# Input-Comparator.net
KiCad netlist of a schematic drawn in Altium Designer
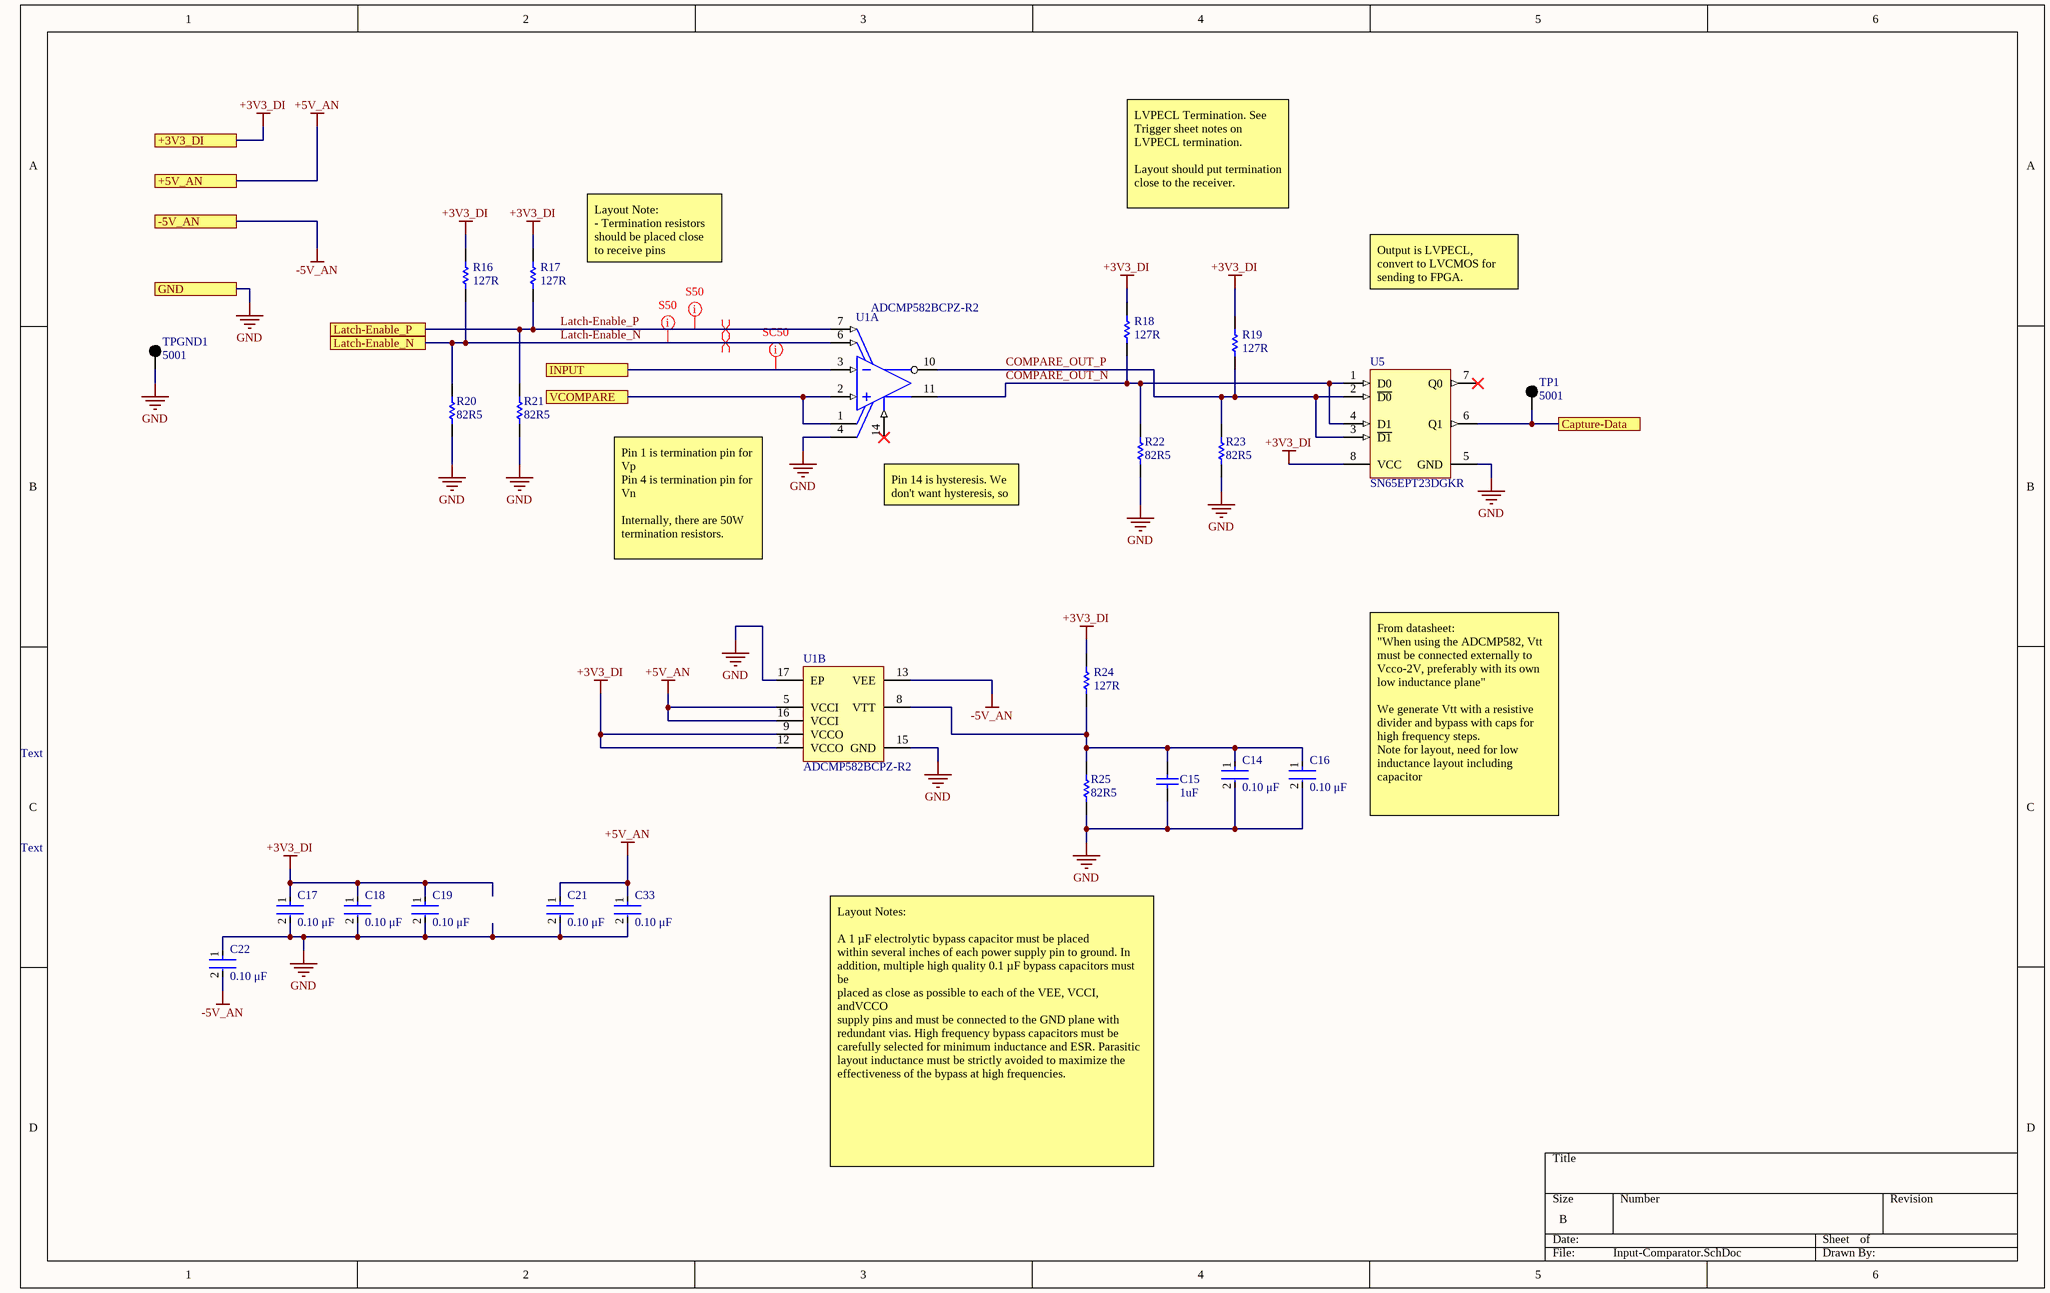
[diagram p0: Input-Comparator.SchDoc]

(export (version "E")
  (design (tool "Eeschema 10.0.6"))
  (components
    (comp (ref "C14")
      (value "C0402C104K8PACTU")
      (footprint "FP-C0402-BB-MFG")
      (description "CAP CER 0.1UF 10V X5R 0402")
      (fields
        (field (name "CAPACITANCE") "0.10 μF")
        (field (name "MANUFACTURER") "Kemet")
        (field (name "TOLERANCE") "0.1")
      )
      (libsource (lib "Altium Content Vault") (part "b4654b650e69147ec39a6b967a45e02"))
    )
    (comp (ref "C15")
      (value "1uF")
      (footprint "CAPC2013X100X50NL20T25")
      (fields (field (name "PART NUMBER") "C0805X105K3RACTU") (field (name "MANUFACTURER") "Kemet"))
      (libsource (lib "Altium Content Vault") (part "CAP"))
    )
    (comp (ref "C16")
      (value "C0402C104K8PACTU")
      (footprint "FP-C0402-BB-MFG")
      (description "CAP CER 0.1UF 10V X5R 0402")
      (fields
        (field (name "CAPACITANCE") "0.10 μF")
        (field (name "MANUFACTURER") "Kemet")
        (field (name "TOLERANCE") "0.1")
      )
      (libsource (lib "Altium Content Vault") (part "b4654b650e69147ec39a6b967a45e02"))
    )
    (comp (ref "C17")
      (value "C0402C104K8PACTU")
      (footprint "FP-C0402-BB-MFG")
      (description "CAP CER 0.1UF 10V X5R 0402")
      (fields
        (field (name "CAPACITANCE") "0.10 μF")
        (field (name "MANUFACTURER") "Kemet")
        (field (name "TOLERANCE") "0.1")
      )
      (libsource (lib "Altium Content Vault") (part "b4654b650e69147ec39a6b967a45e02"))
    )
    (comp (ref "C18")
      (value "C0402C104K8PACTU")
      (footprint "FP-C0402-BB-MFG")
      (description "CAP CER 0.1UF 10V X5R 0402")
      (fields
        (field (name "CAPACITANCE") "0.10 μF")
        (field (name "MANUFACTURER") "Kemet")
        (field (name "TOLERANCE") "0.1")
      )
      (libsource (lib "Altium Content Vault") (part "b4654b650e69147ec39a6b967a45e02"))
    )
    (comp (ref "C19")
      (value "C0402C104K8PACTU")
      (footprint "FP-C0402-BB-MFG")
      (description "CAP CER 0.1UF 10V X5R 0402")
      (fields
        (field (name "CAPACITANCE") "0.10 μF")
        (field (name "MANUFACTURER") "Kemet")
        (field (name "TOLERANCE") "0.1")
      )
      (libsource (lib "Altium Content Vault") (part "b4654b650e69147ec39a6b967a45e02"))
    )
    (comp (ref "C21")
      (value "C0402C104K8PACTU")
      (footprint "FP-C0402-BB-MFG")
      (description "CAP CER 0.1UF 10V X5R 0402")
      (fields
        (field (name "CAPACITANCE") "0.10 μF")
        (field (name "MANUFACTURER") "Kemet")
        (field (name "TOLERANCE") "0.1")
      )
      (libsource (lib "Altium Content Vault") (part "b4654b650e69147ec39a6b967a45e02"))
    )
    (comp (ref "C22")
      (value "C0402C104K8PACTU")
      (footprint "FP-C0402-BB-MFG")
      (description "CAP CER 0.1UF 10V X5R 0402")
      (fields
        (field (name "CAPACITANCE") "0.10 μF")
        (field (name "MANUFACTURER") "Kemet")
        (field (name "TOLERANCE") "0.1")
      )
      (libsource (lib "Altium Content Vault") (part "b4654b650e69147ec39a6b967a45e02"))
    )
    (comp (ref "C33")
      (value "C0402C104K8PACTU")
      (footprint "FP-C0402-BB-MFG")
      (description "CAP CER 0.1UF 10V X5R 0402")
      (fields
        (field (name "CAPACITANCE") "0.10 μF")
        (field (name "MANUFACTURER") "Kemet")
        (field (name "TOLERANCE") "0.1")
      )
      (libsource (lib "Altium Content Vault") (part "b4654b650e69147ec39a6b967a45e02"))
    )
    (comp (ref "R16")
      (value "127R")
      (footprint "RESC1005X40X25LL05T10")
      (fields (field (name "MANUFACTURER") "Yageo / Phycomp") (field (name "PART NUMBER") "RC0402FR-07127RL"))
      (libsource (lib "Altium Content Vault") (part "RES"))
    )
    (comp (ref "R17")
      (value "127R")
      (footprint "RESC1005X40X25LL05T10")
      (fields (field (name "MANUFACTURER") "Yageo / Phycomp") (field (name "PART NUMBER") "RC0402FR-07127RL"))
      (libsource (lib "Altium Content Vault") (part "RES"))
    )
    (comp (ref "R18")
      (value "127R")
      (footprint "RESC1005X40X25LL05T10")
      (fields (field (name "MANUFACTURER") "Yageo / Phycomp") (field (name "PART NUMBER") "RC0402FR-07127RL"))
      (libsource (lib "Altium Content Vault") (part "RES"))
    )
    (comp (ref "R19")
      (value "127R")
      (footprint "RESC1005X40X25LL05T10")
      (fields (field (name "MANUFACTURER") "Yageo / Phycomp") (field (name "PART NUMBER") "RC0402FR-07127RL"))
      (libsource (lib "Altium Content Vault") (part "RES"))
    )
    (comp (ref "R20")
      (value "82R5")
      (footprint "RESC1005X40X25LL05T10")
      (fields (field (name "PART NUMBER") "RC0402FR-0782R5L") (field (name "MANUFACTURER") "Yageo / Phycomp"))
      (libsource (lib "Altium Content Vault") (part "RES"))
    )
    (comp (ref "R21")
      (value "82R5")
      (footprint "RESC1005X40X25LL05T10")
      (fields (field (name "PART NUMBER") "RC0402FR-0782R5L") (field (name "MANUFACTURER") "Yageo / Phycomp"))
      (libsource (lib "Altium Content Vault") (part "RES"))
    )
    (comp (ref "R22")
      (value "82R5")
      (footprint "RESC1005X40X25LL05T10")
      (fields (field (name "PART NUMBER") "RC0402FR-0782R5L") (field (name "MANUFACTURER") "Yageo / Phycomp"))
      (libsource (lib "Altium Content Vault") (part "RES"))
    )
    (comp (ref "R23")
      (value "82R5")
      (footprint "RESC1005X40X25LL05T10")
      (fields (field (name "PART NUMBER") "RC0402FR-0782R5L") (field (name "MANUFACTURER") "Yageo / Phycomp"))
      (libsource (lib "Altium Content Vault") (part "RES"))
    )
    (comp (ref "R24")
      (value "127R")
      (footprint "RESC1005X40X25LL05T10")
      (fields (field (name "MANUFACTURER") "Yageo / Phycomp") (field (name "PART NUMBER") "RC0402FR-07127RL"))
      (libsource (lib "Altium Content Vault") (part "RES"))
    )
    (comp (ref "R25")
      (value "82R5")
      (footprint "RESC1005X40X25LL05T10")
      (fields (field (name "PART NUMBER") "RC0402FR-0782R5L") (field (name "MANUFACTURER") "Yageo / Phycomp"))
      (libsource (lib "Altium Content Vault") (part "RES"))
    )
    (comp (ref "TP1")
      (value "5001")
      (footprint "KSTN-5001")
      (description "Test Point, Black, 1-Pin THD, RoHS, Bulk")
      (fields (field (name "MANUFACTURER") "Keystone"))
      (libsource (lib "Altium Content Vault") (part "KSTN-TP-5001"))
    )
    (comp (ref "TPGND1")
      (value "5001")
      (footprint "KSTN-5001")
      (description "Test Point, Black, 1-Pin THD, RoHS, Bulk")
      (fields (field (name "MANUFACTURER") "Keystone"))
      (libsource (lib "Altium Content Vault") (part "KSTN-TP-5001"))
    )
    (comp (ref "U1")
      (value "ADCMP582BCPZ-R2")
      (footprint "ADI-CP-16-3_L")
      (description "Ultrafast SiGe Voltage Comparator, + / - 5 V, 180 ps Delay, Industrial, 16-pin QFN (CP-16-3), Reel")
      (fields (field (name "MANUFACTURER") "Analog Devices"))
      (libsource (lib "Altium Content Vault") (part "ADI-ADCMP582-CP-16-3"))
    )
    (comp (ref "U5")
      (value "SN65EPT23DGKR")
      (footprint "DGK0008A_L")
      (fields (field (name "MANUFACTURER") "Texas Instruments"))
      (libsource (lib "Altium Content Vault") (part "TI-SN65EPT23-MSOP_DGK-8"))
    )
  )
  (nets
    (net (code "1") (name "+3V3_DI") (class "Default")
      (node (ref "C17") (pin "1") (pinfunction "1_1") (pintype "passive"))
      (node (ref "C18") (pin "1") (pinfunction "1_1") (pintype "passive"))
      (node (ref "C19") (pin "1") (pinfunction "1_1") (pintype "passive"))
      (node (ref "R16") (pin "2") (pinfunction "2_2") (pintype "passive"))
      (node (ref "R17") (pin "2") (pinfunction "2_2") (pintype "passive"))
      (node (ref "R18") (pin "2") (pinfunction "2_2") (pintype "passive"))
      (node (ref "R19") (pin "2") (pinfunction "2_2") (pintype "passive"))
      (node (ref "R24") (pin "2") (pinfunction "2_2") (pintype "passive"))
      (node (ref "U1") (pin "12") (pinfunction "VCCO_12") (pintype "power_in"))
      (node (ref "U1") (pin "9") (pinfunction "VCCO_9") (pintype "power_in"))
      (node (ref "U5") (pin "8") (pinfunction "VCC_8") (pintype "power_in"))
    )
    (net (code "2") (name "+5V_AN") (class "Default")
      (node (ref "C21") (pin "1") (pinfunction "1_1") (pintype "passive"))
      (node (ref "C33") (pin "1") (pinfunction "1_1") (pintype "passive"))
      (node (ref "U1") (pin "16") (pinfunction "VCCI_16") (pintype "power_in"))
      (node (ref "U1") (pin "5") (pinfunction "VCCI_5") (pintype "power_in"))
    )
    (net (code "3") (name "-5V_AN") (class "Default")
      (node (ref "C22") (pin "2") (pinfunction "2_2") (pintype "passive"))
      (node (ref "U1") (pin "13") (pinfunction "VEE_13") (pintype "power_in"))
    )
    (net (code "4") (name "/COMPARE_OUT_N") (class "Default")
      (node (ref "R18") (pin "1") (pinfunction "1_1") (pintype "passive"))
      (node (ref "R22") (pin "2") (pinfunction "2_2") (pintype "passive"))
      (node (ref "U1") (pin "11") (pinfunction "Q_11") (pintype "open_emitter"))
      (node (ref "U5") (pin "1") (pinfunction "D0_1") (pintype "input"))
      (node (ref "U5") (pin "4") (pinfunction "D1_4") (pintype "input"))
    )
    (net (code "5") (name "/COMPARE_OUT_P") (class "Default")
      (node (ref "R19") (pin "1") (pinfunction "1_1") (pintype "passive"))
      (node (ref "R23") (pin "2") (pinfunction "2_2") (pintype "passive"))
      (node (ref "U1") (pin "10") (pinfunction "~{Q}_10") (pintype "open_emitter"))
      (node (ref "U5") (pin "2") (pinfunction "~{D0}_2") (pintype "input"))
      (node (ref "U5") (pin "3") (pinfunction "~{D1}_3") (pintype "input"))
    )
    (net (code "6") (name "/Capture-Data") (class "Default")
      (node (ref "TP1") (pin "1") (pintype "passive"))
      (node (ref "U5") (pin "6") (pinfunction "Q1_6") (pintype "output"))
    )
    (net (code "7") (name "/INPUT") (class "Default")
      (node (ref "U1") (pin "3") (pinfunction "VN_3") (pintype "input"))
    )
    (net (code "8") (name "/Latch-Enable_N") (class "Default")
      (node (ref "R16") (pin "1") (pinfunction "1_1") (pintype "passive"))
      (node (ref "R20") (pin "2") (pinfunction "2_2") (pintype "passive"))
      (node (ref "U1") (pin "6") (pinfunction "~{LE}_6") (pintype "input"))
    )
    (net (code "9") (name "/Latch-Enable_P") (class "Default")
      (node (ref "R17") (pin "1") (pinfunction "1_1") (pintype "passive"))
      (node (ref "R21") (pin "2") (pinfunction "2_2") (pintype "passive"))
      (node (ref "U1") (pin "7") (pinfunction "LE_7") (pintype "input"))
    )
    (net (code "10") (name "/VCOMPARE") (class "Default")
      (node (ref "U1") (pin "1") (pinfunction "VTP_1") (pintype "passive"))
      (node (ref "U1") (pin "2") (pinfunction "VP_2") (pintype "input"))
    )
    (net (code "11") (name "GND") (class "Default")
      (node (ref "C14") (pin "2") (pinfunction "2_2") (pintype "passive"))
      (node (ref "C15") (pin "1") (pinfunction "1_1") (pintype "passive"))
      (node (ref "C16") (pin "2") (pinfunction "2_2") (pintype "passive"))
      (node (ref "C17") (pin "2") (pinfunction "2_2") (pintype "passive"))
      (node (ref "C18") (pin "2") (pinfunction "2_2") (pintype "passive"))
      (node (ref "C19") (pin "2") (pinfunction "2_2") (pintype "passive"))
      (node (ref "C21") (pin "2") (pinfunction "2_2") (pintype "passive"))
      (node (ref "C22") (pin "1") (pinfunction "1_1") (pintype "passive"))
      (node (ref "C33") (pin "2") (pinfunction "2_2") (pintype "passive"))
      (node (ref "R20") (pin "1") (pinfunction "1_1") (pintype "passive"))
      (node (ref "R21") (pin "1") (pinfunction "1_1") (pintype "passive"))
      (node (ref "R22") (pin "1") (pinfunction "1_1") (pintype "passive"))
      (node (ref "R23") (pin "1") (pinfunction "1_1") (pintype "passive"))
      (node (ref "R25") (pin "1") (pinfunction "1_1") (pintype "passive"))
      (node (ref "TPGND1") (pin "1") (pintype "passive"))
      (node (ref "U1") (pin "15") (pinfunction "GND_15") (pintype "power_in"))
      (node (ref "U1") (pin "17") (pinfunction "EP_17") (pintype "passive"))
      (node (ref "U1") (pin "4") (pinfunction "VTN_4") (pintype "passive"))
      (node (ref "U5") (pin "5") (pinfunction "GND_5") (pintype "power_in"))
    )
    (net (code "12") (name "Net-(U1B-VTT)") (class "Default")
      (node (ref "C14") (pin "1") (pinfunction "1_1") (pintype "passive"))
      (node (ref "C15") (pin "2") (pinfunction "2_2") (pintype "passive"))
      (node (ref "C16") (pin "1") (pinfunction "1_1") (pintype "passive"))
      (node (ref "R24") (pin "1") (pinfunction "1_1") (pintype "passive"))
      (node (ref "R25") (pin "2") (pinfunction "2_2") (pintype "passive"))
      (node (ref "U1") (pin "8") (pinfunction "VTT_8") (pintype "power_in"))
    )
    (net (code "13") (name "unconnected-(U1A-HYS-Pad14)") (class "Default")
      (node (ref "U1") (pin "14") (pinfunction "HYS_14") (pintype "input+no_connect"))
    )
    (net (code "14") (name "unconnected-(U5-Q0-Pad7)") (class "Default")
      (node (ref "U5") (pin "7") (pinfunction "Q0_7") (pintype "output+no_connect"))
    )
  )
)
